# cube.net
KiCad netlist of a schematic drawn in EAGLE
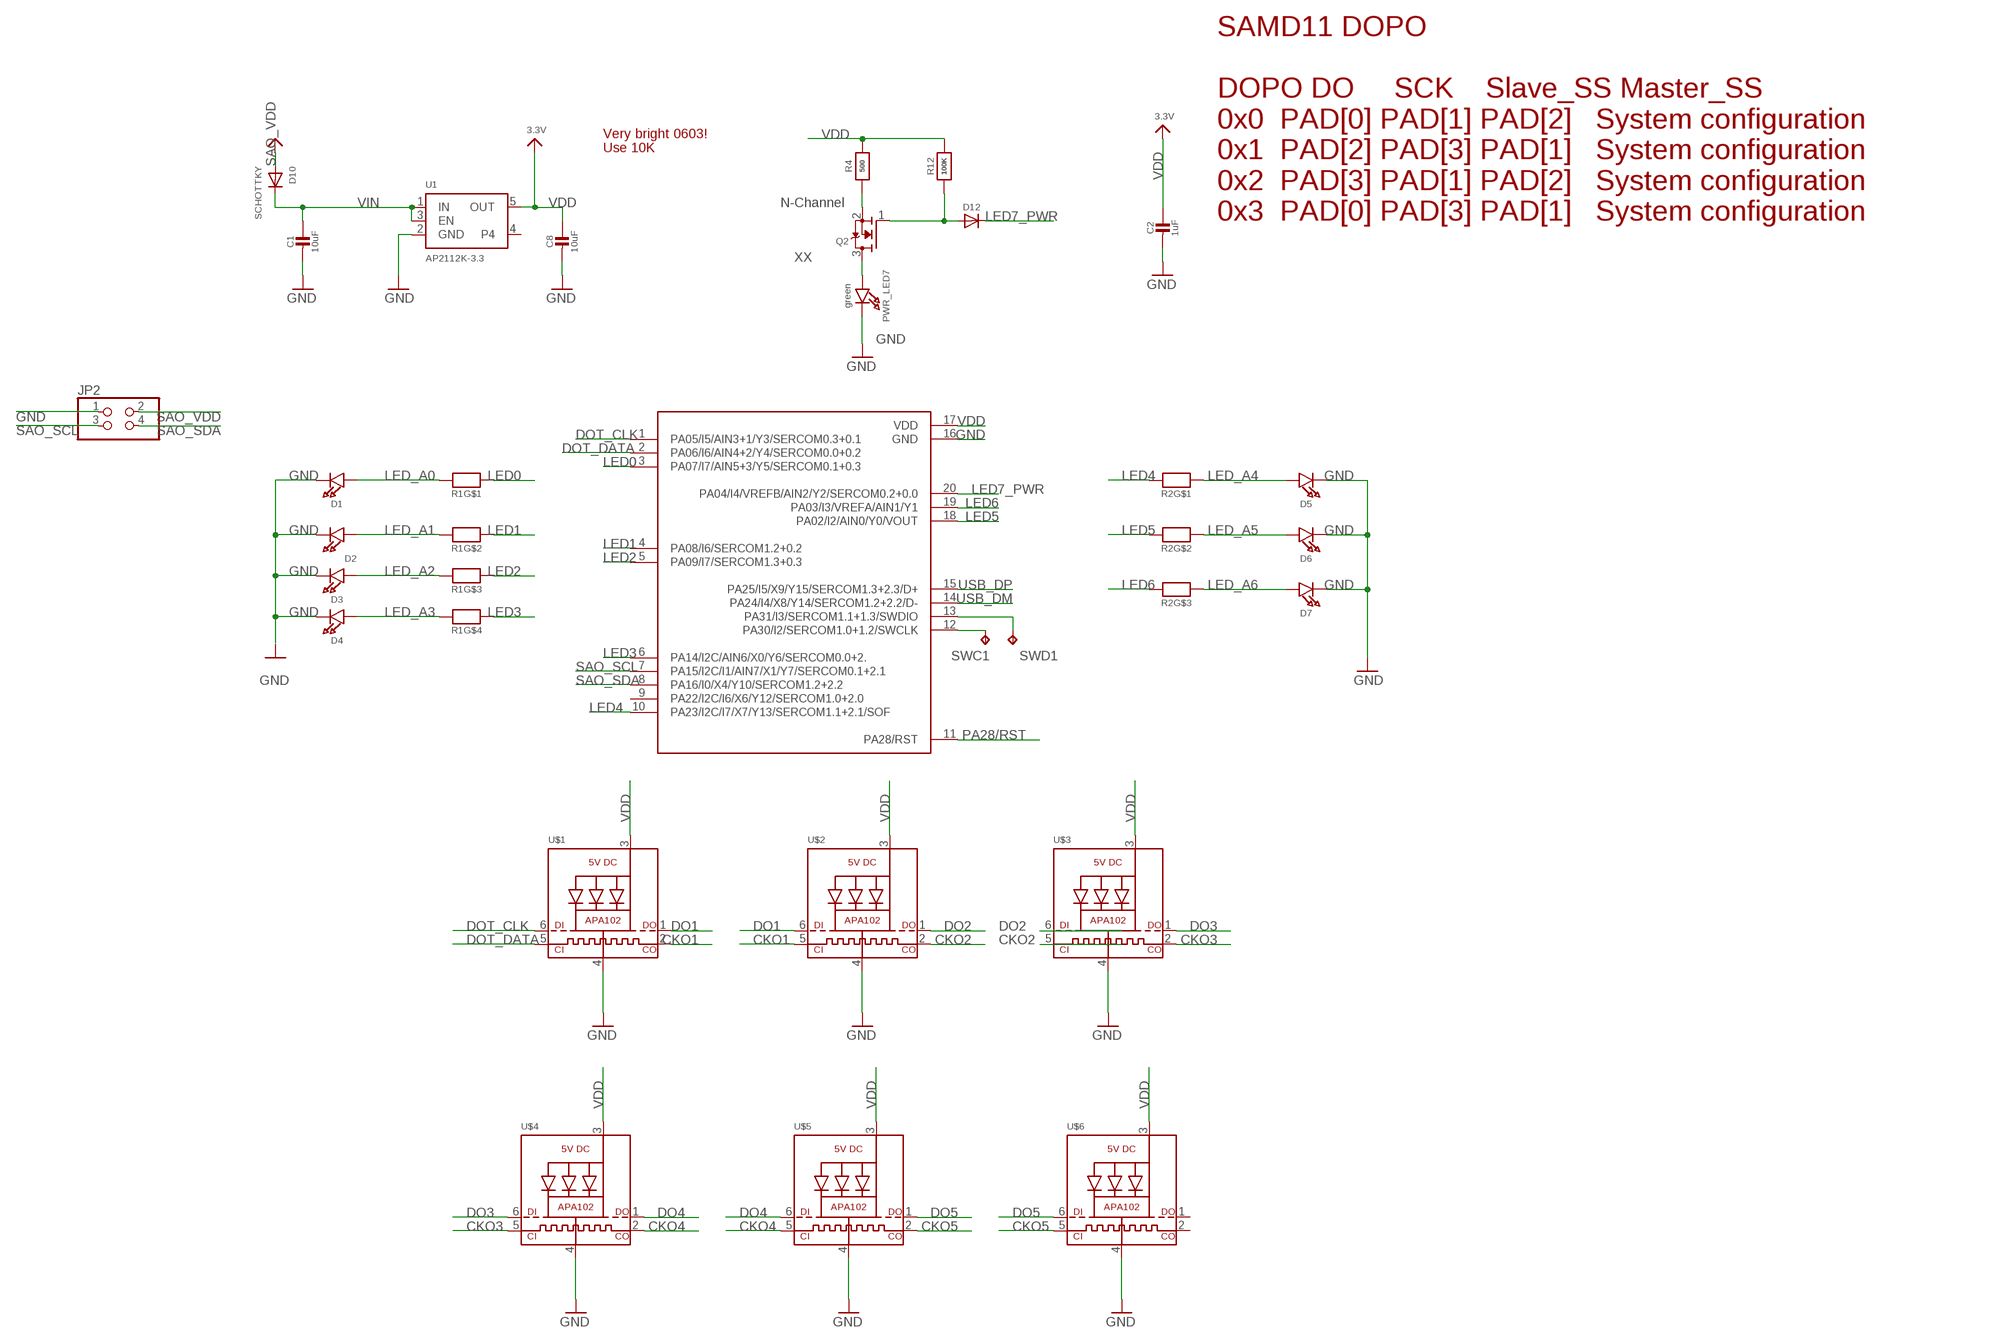
[diagram p0: schematic, sheet 1]

(export (version "E")
  (design (tool "Eeschema 10.0.6"))
  (components
    (comp (ref "C1")
      (value "10uF")
      (footprint "eagle-import:0805-NO")
      (libsource (lib "eagle-import") (part "CAP_CERAMIC0805-NOOUTLINE"))
    )
    (comp (ref "C2")
      (value "1uF")
      (footprint "eagle-import:0603-NO")
      (libsource (lib "eagle-import") (part "CAP_CERAMIC0603_NO"))
    )
    (comp (ref "C8")
      (value "10uF")
      (footprint "eagle-import:0805-NO")
      (libsource (lib "eagle-import") (part "CAP_CERAMIC0805-NOOUTLINE"))
    )
    (comp (ref "D1")
      (value "LED0603_NOOUTLINE")
      (footprint "eagle-import:CHIPLED_0603_NOOUTLINE")
      (libsource (lib "eagle-import") (part "LED0603_NOOUTLINE"))
    )
    (comp (ref "D2")
      (value "LED0603_NOOUTLINE")
      (footprint "eagle-import:CHIPLED_0603_NOOUTLINE")
      (libsource (lib "eagle-import") (part "LED0603_NOOUTLINE"))
    )
    (comp (ref "D3")
      (value "LED0603_NOOUTLINE")
      (footprint "eagle-import:CHIPLED_0603_NOOUTLINE")
      (libsource (lib "eagle-import") (part "LED0603_NOOUTLINE"))
    )
    (comp (ref "D4")
      (value "LED0603_NOOUTLINE")
      (footprint "eagle-import:CHIPLED_0603_NOOUTLINE")
      (libsource (lib "eagle-import") (part "LED0603_NOOUTLINE"))
    )
    (comp (ref "D5")
      (value "LED0603_NOOUTLINE")
      (footprint "eagle-import:CHIPLED_0603_NOOUTLINE")
      (libsource (lib "eagle-import") (part "LED0603_NOOUTLINE"))
    )
    (comp (ref "D6")
      (value "LED0603_NOOUTLINE")
      (footprint "eagle-import:CHIPLED_0603_NOOUTLINE")
      (libsource (lib "eagle-import") (part "LED0603_NOOUTLINE"))
    )
    (comp (ref "D7")
      (value "LED0603_NOOUTLINE")
      (footprint "eagle-import:CHIPLED_0603_NOOUTLINE")
      (libsource (lib "eagle-import") (part "LED0603_NOOUTLINE"))
    )
    (comp (ref "D10")
      (value "SCHOTTKY")
      (footprint "eagle-import:SOD-123FL")
      (libsource (lib "eagle-import") (part "DIODE_SOD-123FL"))
    )
    (comp (ref "D12")
      (value "DIODESOD-323")
      (footprint "eagle-import:SOD-323")
      (libsource (lib "eagle-import") (part "DIODESOD-323"))
    )
    (comp (ref "JP2")
      (value "PINHD-2X2")
      (footprint "eagle-import:2X02")
      (libsource (lib "eagle-import") (part "PINHD-2X2"))
    )
    (comp (ref "PWR_LED7")
      (value "green")
      (footprint "eagle-import:CHIPLED_0603_NOOUTLINE")
      (libsource (lib "eagle-import") (part "LED0603_NOOUTLINE"))
    )
    (comp (ref "Q2")
      (value "MOSFET-NREFLOW")
      (footprint "eagle-import:SOT23-R")
      (libsource (lib "eagle-import") (part "MOSFET-NREFLOW"))
    )
    (comp (ref "R1")
      (value "RESISTOR_4PACK_NO")
      (footprint "eagle-import:RESPACK_4X0603_NO")
      (libsource (lib "eagle-import") (part "RESISTOR_4PACK_NO"))
    )
    (comp (ref "R2")
      (value "RESISTOR_4PACK_NO")
      (footprint "eagle-import:RESPACK_4X0603_NO")
      (libsource (lib "eagle-import") (part "RESISTOR_4PACK_NO"))
    )
    (comp (ref "R4")
      (value "500")
      (footprint "eagle-import:0603-NO")
      (libsource (lib "eagle-import") (part "RESISTOR_0603_NOOUT"))
    )
    (comp (ref "R12")
      (value "100K")
      (footprint "eagle-import:0603-NO")
      (libsource (lib "eagle-import") (part "RESISTOR_0603_NOOUT"))
    )
    (comp (ref "SWC1")
      (value "TPB1,27")
      (footprint "eagle-import:B1,27")
      (libsource (lib "eagle-import") (part "TPB1,27"))
    )
    (comp (ref "SWD1")
      (value "TPB1,27")
      (footprint "eagle-import:B1,27")
      (libsource (lib "eagle-import") (part "TPB1,27"))
    )
    (comp (ref "U$1")
      (value "APA1022020")
      (footprint "eagle-import:APA102_2020")
      (libsource (lib "eagle-import") (part "APA1022020"))
    )
    (comp (ref "U$2")
      (value "APA1022020")
      (footprint "eagle-import:APA102_2020")
      (libsource (lib "eagle-import") (part "APA1022020"))
    )
    (comp (ref "U$3")
      (value "APA1022020")
      (footprint "eagle-import:APA102_2020")
      (libsource (lib "eagle-import") (part "APA1022020"))
    )
    (comp (ref "U$4")
      (value "APA1022020")
      (footprint "eagle-import:APA102_2020")
      (libsource (lib "eagle-import") (part "APA1022020"))
    )
    (comp (ref "U$5")
      (value "APA1022020")
      (footprint "eagle-import:APA102_2020")
      (libsource (lib "eagle-import") (part "APA1022020"))
    )
    (comp (ref "U$6")
      (value "APA1022020")
      (footprint "eagle-import:APA102_2020")
      (libsource (lib "eagle-import") (part "APA1022020"))
    )
    (comp (ref "U$7")
      (value "SOIC20WIDE_ATSAMD11D14A-SS")
      (footprint "eagle-import:SOIC20WIDE_SOIC20WIDE")
      (libsource (lib "eagle-import") (part "SOIC20WIDE_ATSAMD11D14A-SS"))
    )
    (comp (ref "U1")
      (value "AP2112K-3.3")
      (footprint "eagle-import:SOT23-5")
      (libsource (lib "eagle-import") (part "VREG_SOT23-5"))
    )
  )
  (nets
    (net (code "1") (name "/CKO1") (class "Default")
      (node (ref "U$1") (pin "2") (pinfunction "CKO_2") (pintype "output"))
      (node (ref "U$2") (pin "5") (pinfunction "CKI_5") (pintype "input"))
    )
    (net (code "2") (name "/CKO2") (class "Default")
      (node (ref "U$2") (pin "2") (pinfunction "CKO_2") (pintype "output"))
      (node (ref "U$3") (pin "5") (pinfunction "CKI_5") (pintype "input"))
    )
    (net (code "3") (name "/CKO3") (class "Default")
      (node (ref "U$3") (pin "2") (pinfunction "CKO_2") (pintype "output"))
      (node (ref "U$4") (pin "5") (pinfunction "CKI_5") (pintype "input"))
    )
    (net (code "4") (name "/CKO4") (class "Default")
      (node (ref "U$4") (pin "2") (pinfunction "CKO_2") (pintype "output"))
      (node (ref "U$5") (pin "5") (pinfunction "CKI_5") (pintype "input"))
    )
    (net (code "5") (name "/CKO5") (class "Default")
      (node (ref "U$5") (pin "2") (pinfunction "CKO_2") (pintype "output"))
      (node (ref "U$6") (pin "5") (pinfunction "CKI_5") (pintype "input"))
    )
    (net (code "6") (name "/DO1") (class "Default")
      (node (ref "U$1") (pin "1") (pinfunction "DO_1") (pintype "output"))
      (node (ref "U$2") (pin "6") (pinfunction "DI_6") (pintype "input"))
    )
    (net (code "7") (name "/DO2") (class "Default")
      (node (ref "U$2") (pin "1") (pinfunction "DO_1") (pintype "output"))
      (node (ref "U$3") (pin "6") (pinfunction "DI_6") (pintype "input"))
    )
    (net (code "8") (name "/DO3") (class "Default")
      (node (ref "U$3") (pin "1") (pinfunction "DO_1") (pintype "output"))
      (node (ref "U$4") (pin "6") (pinfunction "DI_6") (pintype "input"))
    )
    (net (code "9") (name "/DO4") (class "Default")
      (node (ref "U$4") (pin "1") (pinfunction "DO_1") (pintype "output"))
      (node (ref "U$5") (pin "6") (pinfunction "DI_6") (pintype "input"))
    )
    (net (code "10") (name "/DO5") (class "Default")
      (node (ref "U$5") (pin "1") (pinfunction "DO_1") (pintype "output"))
      (node (ref "U$6") (pin "6") (pinfunction "DI_6") (pintype "input"))
    )
    (net (code "11") (name "/DOT_CLK") (class "Default")
      (node (ref "U$1") (pin "6") (pinfunction "DI_6") (pintype "input"))
      (node (ref "U$7") (pin "1") (pinfunction "PA05/I5/AIN3+1/Y3/SERCOM0.3+0.1_1") (pintype "bidirectional"))
    )
    (net (code "12") (name "/DOT_DATA") (class "Default")
      (node (ref "U$1") (pin "5") (pinfunction "CKI_5") (pintype "input"))
      (node (ref "U$7") (pin "2") (pinfunction "PA06/I6/AIN4+2/Y4/SERCOM0.0+0.2_2") (pintype "bidirectional"))
    )
    (net (code "13") (name "/LED0") (class "Default")
      (node (ref "R1") (pin "1") (pinfunction "1_1") (pintype "passive"))
      (node (ref "U$7") (pin "3") (pinfunction "PA07/I7/AIN5+3/Y5/SERCOM0.1+0.3_3") (pintype "bidirectional"))
    )
    (net (code "14") (name "/LED1") (class "Default")
      (node (ref "R1") (pin "2") (pinfunction "1_2") (pintype "passive"))
      (node (ref "U$7") (pin "4") (pinfunction "PA08/I6/SERCOM1.2+0.2_4") (pintype "bidirectional"))
    )
    (net (code "15") (name "/LED2") (class "Default")
      (node (ref "R1") (pin "3") (pinfunction "1_3") (pintype "passive"))
      (node (ref "U$7") (pin "5") (pinfunction "PA09/I7/SERCOM1.3+0.3_5") (pintype "bidirectional"))
    )
    (net (code "16") (name "/LED3") (class "Default")
      (node (ref "R1") (pin "4") (pinfunction "1_4") (pintype "passive"))
      (node (ref "U$7") (pin "6") (pinfunction "PA14/I2C/AIN6/X0/Y6/SERCOM0.0+2._6") (pintype "bidirectional"))
    )
    (net (code "17") (name "/LED4") (class "Default")
      (node (ref "R2") (pin "1") (pinfunction "1_1") (pintype "passive"))
      (node (ref "U$7") (pin "10") (pinfunction "PA23/I2C/I7/X7/Y13/SERCOM1.1+2.1/SOF_10") (pintype "bidirectional"))
    )
    (net (code "18") (name "/LED5") (class "Default")
      (node (ref "R2") (pin "2") (pinfunction "1_2") (pintype "passive"))
      (node (ref "U$7") (pin "18") (pinfunction "PA02/I2/AIN0/Y0/VOUT_18") (pintype "bidirectional"))
    )
    (net (code "19") (name "/LED6") (class "Default")
      (node (ref "R2") (pin "3") (pinfunction "1_3") (pintype "passive"))
      (node (ref "U$7") (pin "19") (pinfunction "PA03/I3/VREFA/AIN1/Y1_19") (pintype "bidirectional"))
    )
    (net (code "20") (name "/LED7_PWR") (class "Default")
      (node (ref "D12") (pin "C") (pinfunction "C_C") (pintype "passive"))
      (node (ref "U$7") (pin "20") (pinfunction "PA04/I4/VREFB/AIN2/Y2/SERCOM0.2+0.0_20") (pintype "bidirectional"))
    )
    (net (code "21") (name "/LED_A0") (class "Default")
      (node (ref "D1") (pin "A") (pinfunction "A_A") (pintype "passive"))
      (node (ref "R1") (pin "8") (pinfunction "2_8") (pintype "passive"))
    )
    (net (code "22") (name "/LED_A1") (class "Default")
      (node (ref "D2") (pin "A") (pinfunction "A_A") (pintype "passive"))
      (node (ref "R1") (pin "7") (pinfunction "2_7") (pintype "passive"))
    )
    (net (code "23") (name "/LED_A2") (class "Default")
      (node (ref "D3") (pin "A") (pinfunction "A_A") (pintype "passive"))
      (node (ref "R1") (pin "6") (pinfunction "2_6") (pintype "passive"))
    )
    (net (code "24") (name "/LED_A3") (class "Default")
      (node (ref "D4") (pin "A") (pinfunction "A_A") (pintype "passive"))
      (node (ref "R1") (pin "5") (pinfunction "2_5") (pintype "passive"))
    )
    (net (code "25") (name "/LED_A4") (class "Default")
      (node (ref "D5") (pin "A") (pinfunction "A_A") (pintype "passive"))
      (node (ref "R2") (pin "8") (pinfunction "2_8") (pintype "passive"))
    )
    (net (code "26") (name "/LED_A5") (class "Default")
      (node (ref "D6") (pin "A") (pinfunction "A_A") (pintype "passive"))
      (node (ref "R2") (pin "7") (pinfunction "2_7") (pintype "passive"))
    )
    (net (code "27") (name "/LED_A6") (class "Default")
      (node (ref "D7") (pin "A") (pinfunction "A_A") (pintype "passive"))
      (node (ref "R2") (pin "6") (pinfunction "2_6") (pintype "passive"))
    )
    (net (code "28") (name "/PA28{slash}RST") (class "Default")
      (node (ref "U$7") (pin "11") (pinfunction "PA28/RST_11") (pintype "bidirectional"))
    )
    (net (code "29") (name "/SAO_SCL") (class "Default")
      (node (ref "JP2") (pin "3") (pinfunction "3_3") (pintype "passive"))
      (node (ref "U$7") (pin "7") (pinfunction "PA15/I2C/I1/AIN7/X1/Y7/SERCOM0.1+2.1_7") (pintype "bidirectional"))
    )
    (net (code "30") (name "/SAO_SDA") (class "Default")
      (node (ref "JP2") (pin "4") (pinfunction "4_4") (pintype "passive"))
      (node (ref "U$7") (pin "8") (pinfunction "PA16/I0/X4/Y10/SERCOM1.2+2.2_8") (pintype "bidirectional"))
    )
    (net (code "31") (name "/USB_DM") (class "Default")
      (node (ref "U$7") (pin "14") (pinfunction "PA24/I4/X8/Y14/SERCOM1.2+2.2/D-_14") (pintype "bidirectional"))
    )
    (net (code "32") (name "/USB_DP") (class "Default")
      (node (ref "U$7") (pin "15") (pinfunction "PA25/I5/X9/Y15/SERCOM1.3+2.3/D+_15") (pintype "bidirectional"))
    )
    (net (code "33") (name "/VIN") (class "Default")
      (node (ref "C1") (pin "1") (pinfunction "1_1") (pintype "passive"))
      (node (ref "D10") (pin "C") (pinfunction "C_C") (pintype "passive"))
      (node (ref "U1") (pin "1") (pinfunction "IN_1") (pintype "power_in"))
      (node (ref "U1") (pin "3") (pinfunction "EN_3") (pintype "input"))
    )
    (net (code "34") (name "/XX") (class "Default")
      (node (ref "PWR_LED7") (pin "A") (pinfunction "A_A") (pintype "passive"))
      (node (ref "Q2") (pin "3") (pinfunction "D_3") (pintype "bidirectional"))
    )
    (net (code "35") (name "3.3V") (class "Default")
      (node (ref "C2") (pin "1") (pinfunction "1_1") (pintype "passive"))
      (node (ref "C8") (pin "1") (pinfunction "1_1") (pintype "passive"))
      (node (ref "R12") (pin "2") (pinfunction "2_2") (pintype "passive"))
      (node (ref "R4") (pin "2") (pinfunction "2_2") (pintype "passive"))
      (node (ref "U$1") (pin "3") (pinfunction "VDD_3") (pintype "power_in"))
      (node (ref "U$2") (pin "3") (pinfunction "VDD_3") (pintype "power_in"))
      (node (ref "U$3") (pin "3") (pinfunction "VDD_3") (pintype "power_in"))
      (node (ref "U$4") (pin "3") (pinfunction "VDD_3") (pintype "power_in"))
      (node (ref "U$5") (pin "3") (pinfunction "VDD_3") (pintype "power_in"))
      (node (ref "U$6") (pin "3") (pinfunction "VDD_3") (pintype "power_in"))
      (node (ref "U$7") (pin "17") (pinfunction "VDD_17") (pintype "power_in"))
      (node (ref "U1") (pin "5") (pinfunction "OUT_5") (pintype "power_in"))
    )
    (net (code "36") (name "GND") (class "Default")
      (node (ref "C1") (pin "2") (pinfunction "2_2") (pintype "passive"))
      (node (ref "C2") (pin "2") (pinfunction "2_2") (pintype "passive"))
      (node (ref "C8") (pin "2") (pinfunction "2_2") (pintype "passive"))
      (node (ref "D1") (pin "C") (pinfunction "C_C") (pintype "passive"))
      (node (ref "D2") (pin "C") (pinfunction "C_C") (pintype "passive"))
      (node (ref "D3") (pin "C") (pinfunction "C_C") (pintype "passive"))
      (node (ref "D4") (pin "C") (pinfunction "C_C") (pintype "passive"))
      (node (ref "D5") (pin "C") (pinfunction "C_C") (pintype "passive"))
      (node (ref "D6") (pin "C") (pinfunction "C_C") (pintype "passive"))
      (node (ref "D7") (pin "C") (pinfunction "C_C") (pintype "passive"))
      (node (ref "JP2") (pin "1") (pinfunction "1_1") (pintype "passive"))
      (node (ref "PWR_LED7") (pin "C") (pinfunction "C_C") (pintype "passive"))
      (node (ref "U$1") (pin "4") (pinfunction "GND_4") (pintype "power_in"))
      (node (ref "U$2") (pin "4") (pinfunction "GND_4") (pintype "power_in"))
      (node (ref "U$3") (pin "4") (pinfunction "GND_4") (pintype "power_in"))
      (node (ref "U$4") (pin "4") (pinfunction "GND_4") (pintype "power_in"))
      (node (ref "U$5") (pin "4") (pinfunction "GND_4") (pintype "power_in"))
      (node (ref "U$6") (pin "4") (pinfunction "GND_4") (pintype "power_in"))
      (node (ref "U$7") (pin "16") (pinfunction "GND_16") (pintype "bidirectional"))
      (node (ref "U1") (pin "2") (pinfunction "GND_2") (pintype "power_in"))
    )
    (net (code "37") (name "Net-(Q2-G)") (class "Default")
      (node (ref "D12") (pin "A") (pinfunction "A_A") (pintype "passive"))
      (node (ref "Q2") (pin "1") (pinfunction "G_1") (pintype "bidirectional"))
      (node (ref "R12") (pin "1") (pinfunction "1_1") (pintype "passive"))
    )
    (net (code "38") (name "Net-(Q2-S)") (class "Default")
      (node (ref "Q2") (pin "2") (pinfunction "S_2") (pintype "bidirectional"))
      (node (ref "R4") (pin "1") (pinfunction "1_1") (pintype "passive"))
    )
    (net (code "39") (name "Net-(U$7-PA30{slash}I2{slash}SERCOM1.0+1.2{slash}SWCLK)") (class "Default")
      (node (ref "SWC1") (pin "TP") (pinfunction "TP_TP") (pintype "input"))
      (node (ref "U$7") (pin "12") (pinfunction "PA30/I2/SERCOM1.0+1.2/SWCLK_12") (pintype "bidirectional"))
    )
    (net (code "40") (name "Net-(U$7-PA31{slash}I3{slash}SERCOM1.1+1.3{slash}SWDIO)") (class "Default")
      (node (ref "SWD1") (pin "TP") (pinfunction "TP_TP") (pintype "input"))
      (node (ref "U$7") (pin "13") (pinfunction "PA31/I3/SERCOM1.1+1.3/SWDIO_13") (pintype "bidirectional"))
    )
    (net (code "41") (name "VBAT") (class "Default")
      (node (ref "D10") (pin "A") (pinfunction "A_A") (pintype "passive"))
      (node (ref "JP2") (pin "2") (pinfunction "2_2") (pintype "passive"))
    )
    (net (code "42") (name "unconnected-(U$6-CKO-Pad2)") (class "Default")
      (node (ref "U$6") (pin "2") (pinfunction "CKO_2") (pintype "output"))
    )
    (net (code "43") (name "unconnected-(U$6-DO-Pad1)") (class "Default")
      (node (ref "U$6") (pin "1") (pinfunction "DO_1") (pintype "output"))
    )
    (net (code "44") (name "unconnected-(U$7-PA22{slash}I2C{slash}I6{slash}X6{slash}Y12{slash}SERCOM1.0+2.0-Pad9)") (class "Default")
      (node (ref "U$7") (pin "9") (pinfunction "PA22/I2C/I6/X6/Y12/SERCOM1.0+2.0_9") (pintype "bidirectional"))
    )
    (net (code "45") (name "unconnected-(U1-P4-Pad4)") (class "Default")
      (node (ref "U1") (pin "4") (pinfunction "P4_4") (pintype "bidirectional"))
    )
  )
)
